# Esquema_final.net
KiCad netlist of a schematic drawn in Altium Designer
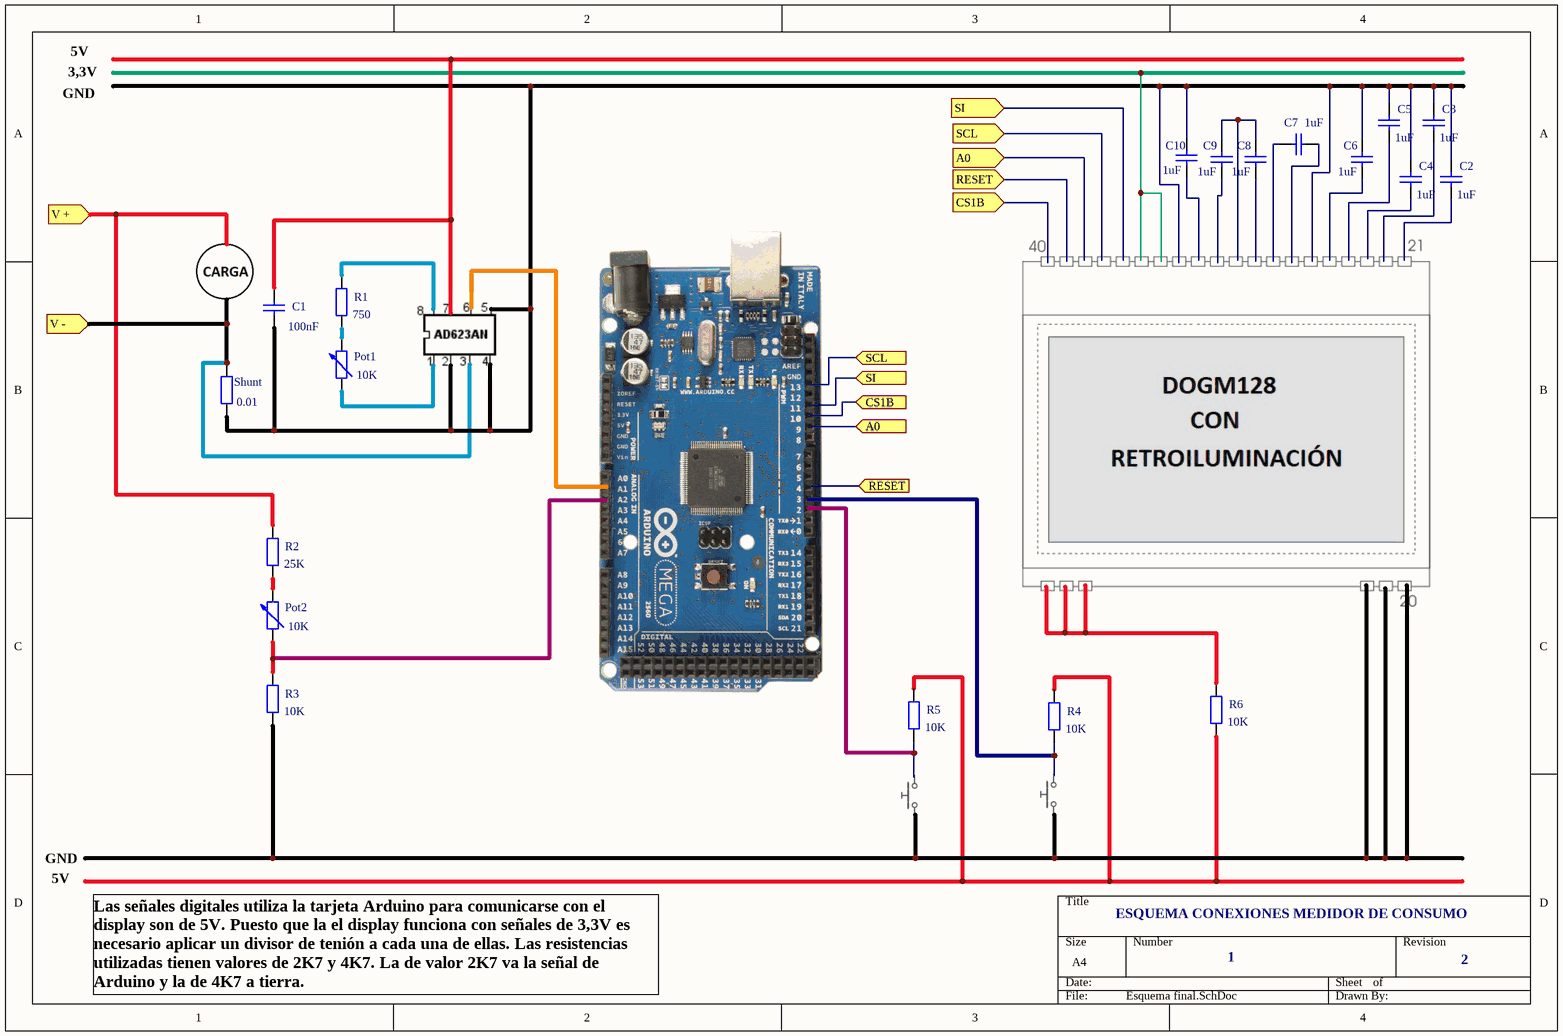
[diagram p0: Esquema final.SchDoc]

(export (version "E")
  (design (tool "Eeschema 10.0.6"))
  (components
    (comp (ref "C1")
      (value "100nF")
      (footprint "RAD-0.3")
      (description "Capacitor")
      (fields (field (name "Comment") "Cap") (field (name "PUBLISHER") "Altium Limited"))
      (libsource (lib "Miscellaneous Devices") (part "Cap"))
    )
    (comp (ref "C2")
      (value "1uF")
      (footprint "RAD-0.3")
      (description "Capacitor")
      (fields (field (name "Comment") "Cap") (field (name "PUBLISHER") "Altium Limited"))
      (libsource (lib "Miscellaneous Devices") (part "Cap"))
    )
    (comp (ref "C3")
      (value "1uF")
      (footprint "RAD-0.3")
      (description "Capacitor")
      (fields (field (name "Comment") "Cap") (field (name "PUBLISHER") "Altium Limited"))
      (libsource (lib "Miscellaneous Devices") (part "Cap"))
    )
    (comp (ref "C4")
      (value "1uF")
      (footprint "RAD-0.3")
      (description "Capacitor")
      (fields (field (name "Comment") "Cap") (field (name "PUBLISHER") "Altium Limited"))
      (libsource (lib "Miscellaneous Devices") (part "Cap"))
    )
    (comp (ref "C5")
      (value "1uF")
      (footprint "RAD-0.3")
      (description "Capacitor")
      (fields (field (name "Comment") "Cap") (field (name "PUBLISHER") "Altium Limited"))
      (libsource (lib "Miscellaneous Devices") (part "Cap"))
    )
    (comp (ref "C6")
      (value "1uF")
      (footprint "RAD-0.3")
      (description "Capacitor")
      (fields (field (name "Comment") "Cap") (field (name "PUBLISHER") "Altium Limited"))
      (libsource (lib "Miscellaneous Devices") (part "Cap"))
    )
    (comp (ref "C7")
      (value "1uF")
      (footprint "RAD-0.3")
      (description "Capacitor")
      (fields (field (name "Comment") "Cap") (field (name "PUBLISHER") "Altium Limited"))
      (libsource (lib "Miscellaneous Devices") (part "Cap"))
    )
    (comp (ref "C8")
      (value "1uF")
      (footprint "RAD-0.3")
      (description "Capacitor")
      (fields (field (name "Comment") "Cap") (field (name "PUBLISHER") "Altium Limited"))
      (libsource (lib "Miscellaneous Devices") (part "Cap"))
    )
    (comp (ref "C9")
      (value "1uF")
      (footprint "RAD-0.3")
      (description "Capacitor")
      (fields (field (name "Comment") "Cap") (field (name "PUBLISHER") "Altium Limited"))
      (libsource (lib "Miscellaneous Devices") (part "Cap"))
    )
    (comp (ref "C10")
      (value "1uF")
      (footprint "RAD-0.3")
      (description "Capacitor")
      (fields (field (name "Comment") "Cap") (field (name "PUBLISHER") "Altium Limited"))
      (libsource (lib "Miscellaneous Devices") (part "Cap"))
    )
    (comp (ref "Pot1")
      (value "10K")
      (footprint "AXIAL-0.6")
      (description "Variable Resistor")
      (fields (field (name "Comment") "Res Adj2") (field (name "PUBLISHER") "Altium Limited"))
      (libsource (lib "Miscellaneous Devices") (part "Res Adj2"))
    )
    (comp (ref "Pot2")
      (value "10K")
      (footprint "AXIAL-0.6")
      (description "Variable Resistor")
      (fields (field (name "Comment") "Res Adj2") (field (name "PUBLISHER") "Altium Limited"))
      (libsource (lib "Miscellaneous Devices") (part "Res Adj2"))
    )
    (comp (ref "R1")
      (value "750")
      (footprint "AXIAL-0.4")
      (description "Resistor")
      (fields (field (name "Comment") "Res2") (field (name "PUBLISHER") "Altium Limited"))
      (libsource (lib "Miscellaneous Devices") (part "Res2"))
    )
    (comp (ref "R2")
      (value "25K")
      (footprint "AXIAL-0.4")
      (description "Resistor")
      (fields (field (name "Comment") "Res2") (field (name "PUBLISHER") "Altium Limited"))
      (libsource (lib "Miscellaneous Devices") (part "Res2"))
    )
    (comp (ref "R3")
      (value "10K")
      (footprint "AXIAL-0.4")
      (description "Resistor")
      (fields (field (name "Comment") "Res2") (field (name "PUBLISHER") "Altium Limited"))
      (libsource (lib "Miscellaneous Devices") (part "Res2"))
    )
    (comp (ref "R4")
      (value "10K")
      (footprint "AXIAL-0.4")
      (description "Resistor")
      (fields (field (name "Comment") "Res2") (field (name "PUBLISHER") "Altium Limited"))
      (libsource (lib "Miscellaneous Devices") (part "Res2"))
    )
    (comp (ref "R5")
      (value "10K")
      (footprint "AXIAL-0.4")
      (description "Resistor")
      (fields (field (name "Comment") "Res2") (field (name "PUBLISHER") "Altium Limited"))
      (libsource (lib "Miscellaneous Devices") (part "Res2"))
    )
    (comp (ref "R6")
      (value "10K")
      (footprint "AXIAL-0.4")
      (description "Resistor")
      (fields (field (name "Comment") "Res2") (field (name "PUBLISHER") "Altium Limited"))
      (libsource (lib "Miscellaneous Devices") (part "Res2"))
    )
    (comp (ref "Shunt")
      (value "0.01")
      (footprint "AXIAL-0.4")
      (description "Resistor")
      (fields (field (name "Comment") "Res2") (field (name "PUBLISHER") "Altium Limited"))
      (libsource (lib "Miscellaneous Devices") (part "Res2"))
    )
  )
  (nets
    (net (code "6") (name "/V +") (class "Default")
      (node (ref "R2") (pin "2") (pinfunction "2_2") (pintype "passive"))
    )
    (net (code "7") (name "/V -") (class "Default")
      (node (ref "Shunt") (pin "2") (pinfunction "2_2") (pintype "passive"))
    )
    (net (code "8") (name "Net-(C1-Pad1)") (class "Default")
      (node (ref "C1") (pin "1") (pinfunction "1_1") (pintype "passive"))
      (node (ref "C10") (pin "2") (pinfunction "2_2") (pintype "passive"))
      (node (ref "C2") (pin "2") (pinfunction "2_2") (pintype "passive"))
      (node (ref "C3") (pin "2") (pinfunction "2_2") (pintype "passive"))
      (node (ref "C4") (pin "2") (pinfunction "2_2") (pintype "passive"))
      (node (ref "C5") (pin "2") (pinfunction "2_2") (pintype "passive"))
      (node (ref "C6") (pin "2") (pinfunction "2_2") (pintype "passive"))
      (node (ref "Shunt") (pin "1") (pinfunction "1_1") (pintype "passive"))
    )
    (net (code "9") (name "Net-(C8-Pad2)") (class "Default")
      (node (ref "C8") (pin "2") (pinfunction "2_2") (pintype "passive"))
      (node (ref "C9") (pin "2") (pinfunction "2_2") (pintype "passive"))
    )
    (net (code "10") (name "Net-(Pot1-Pad2)") (class "Default")
      (node (ref "Pot1") (pin "2") (pinfunction "2_2") (pintype "passive"))
      (node (ref "R1") (pin "1") (pinfunction "1_1") (pintype "passive"))
    )
    (net (code "11") (name "Net-(Pot2-Pad1)") (class "Default")
      (node (ref "Pot2") (pin "1") (pinfunction "1_1") (pintype "passive"))
      (node (ref "R3") (pin "2") (pinfunction "2_2") (pintype "passive"))
    )
    (net (code "12") (name "Net-(Pot2-Pad2)") (class "Default")
      (node (ref "Pot2") (pin "2") (pinfunction "2_2") (pintype "passive"))
      (node (ref "R2") (pin "1") (pinfunction "1_1") (pintype "passive"))
    )
    (net (code "13") (name "Net-(R4-Pad2)") (class "Default")
      (node (ref "R4") (pin "2") (pinfunction "2_2") (pintype "passive"))
      (node (ref "R5") (pin "2") (pinfunction "2_2") (pintype "passive"))
      (node (ref "R6") (pin "1") (pinfunction "1_1") (pintype "passive"))
    )
    (net (code "14") (name "unconnected-(C1-Pad2)") (class "Default")
      (node (ref "C1") (pin "2") (pinfunction "2_2") (pintype "passive"))
    )
    (net (code "15") (name "unconnected-(C2-Pad1)") (class "Default")
      (node (ref "C2") (pin "1") (pinfunction "1_1") (pintype "passive"))
    )
    (net (code "16") (name "unconnected-(C3-Pad1)") (class "Default")
      (node (ref "C3") (pin "1") (pinfunction "1_1") (pintype "passive"))
    )
    (net (code "17") (name "unconnected-(C4-Pad1)") (class "Default")
      (node (ref "C4") (pin "1") (pinfunction "1_1") (pintype "passive"))
    )
    (net (code "18") (name "unconnected-(C5-Pad1)") (class "Default")
      (node (ref "C5") (pin "1") (pinfunction "1_1") (pintype "passive"))
    )
    (net (code "19") (name "unconnected-(C6-Pad1)") (class "Default")
      (node (ref "C6") (pin "1") (pinfunction "1_1") (pintype "passive"))
    )
    (net (code "20") (name "unconnected-(C7-Pad1)") (class "Default")
      (node (ref "C7") (pin "1") (pinfunction "1_1") (pintype "passive"))
    )
    (net (code "21") (name "unconnected-(C7-Pad2)") (class "Default")
      (node (ref "C7") (pin "2") (pinfunction "2_2") (pintype "passive"))
    )
    (net (code "22") (name "unconnected-(C8-Pad1)") (class "Default")
      (node (ref "C8") (pin "1") (pinfunction "1_1") (pintype "passive"))
    )
    (net (code "23") (name "unconnected-(C9-Pad1)") (class "Default")
      (node (ref "C9") (pin "1") (pinfunction "1_1") (pintype "passive"))
    )
    (net (code "24") (name "unconnected-(C10-Pad1)") (class "Default")
      (node (ref "C10") (pin "1") (pinfunction "1_1") (pintype "passive"))
    )
    (net (code "25") (name "unconnected-(Pot1-Pad1)") (class "Default")
      (node (ref "Pot1") (pin "1") (pinfunction "1_1") (pintype "passive"))
    )
    (net (code "26") (name "unconnected-(R1-Pad2)") (class "Default")
      (node (ref "R1") (pin "2") (pinfunction "2_2") (pintype "passive"))
    )
    (net (code "27") (name "unconnected-(R3-Pad1)") (class "Default")
      (node (ref "R3") (pin "1") (pinfunction "1_1") (pintype "passive"))
    )
    (net (code "28") (name "unconnected-(R4-Pad1)") (class "Default")
      (node (ref "R4") (pin "1") (pinfunction "1_1") (pintype "passive"))
    )
    (net (code "29") (name "unconnected-(R5-Pad1)") (class "Default")
      (node (ref "R5") (pin "1") (pinfunction "1_1") (pintype "passive"))
    )
    (net (code "30") (name "unconnected-(R6-Pad2)") (class "Default")
      (node (ref "R6") (pin "2") (pinfunction "2_2") (pintype "passive"))
    )
  )
)
